# io-board-a-3.net
KiCad netlist of a schematic drawn in EAGLE
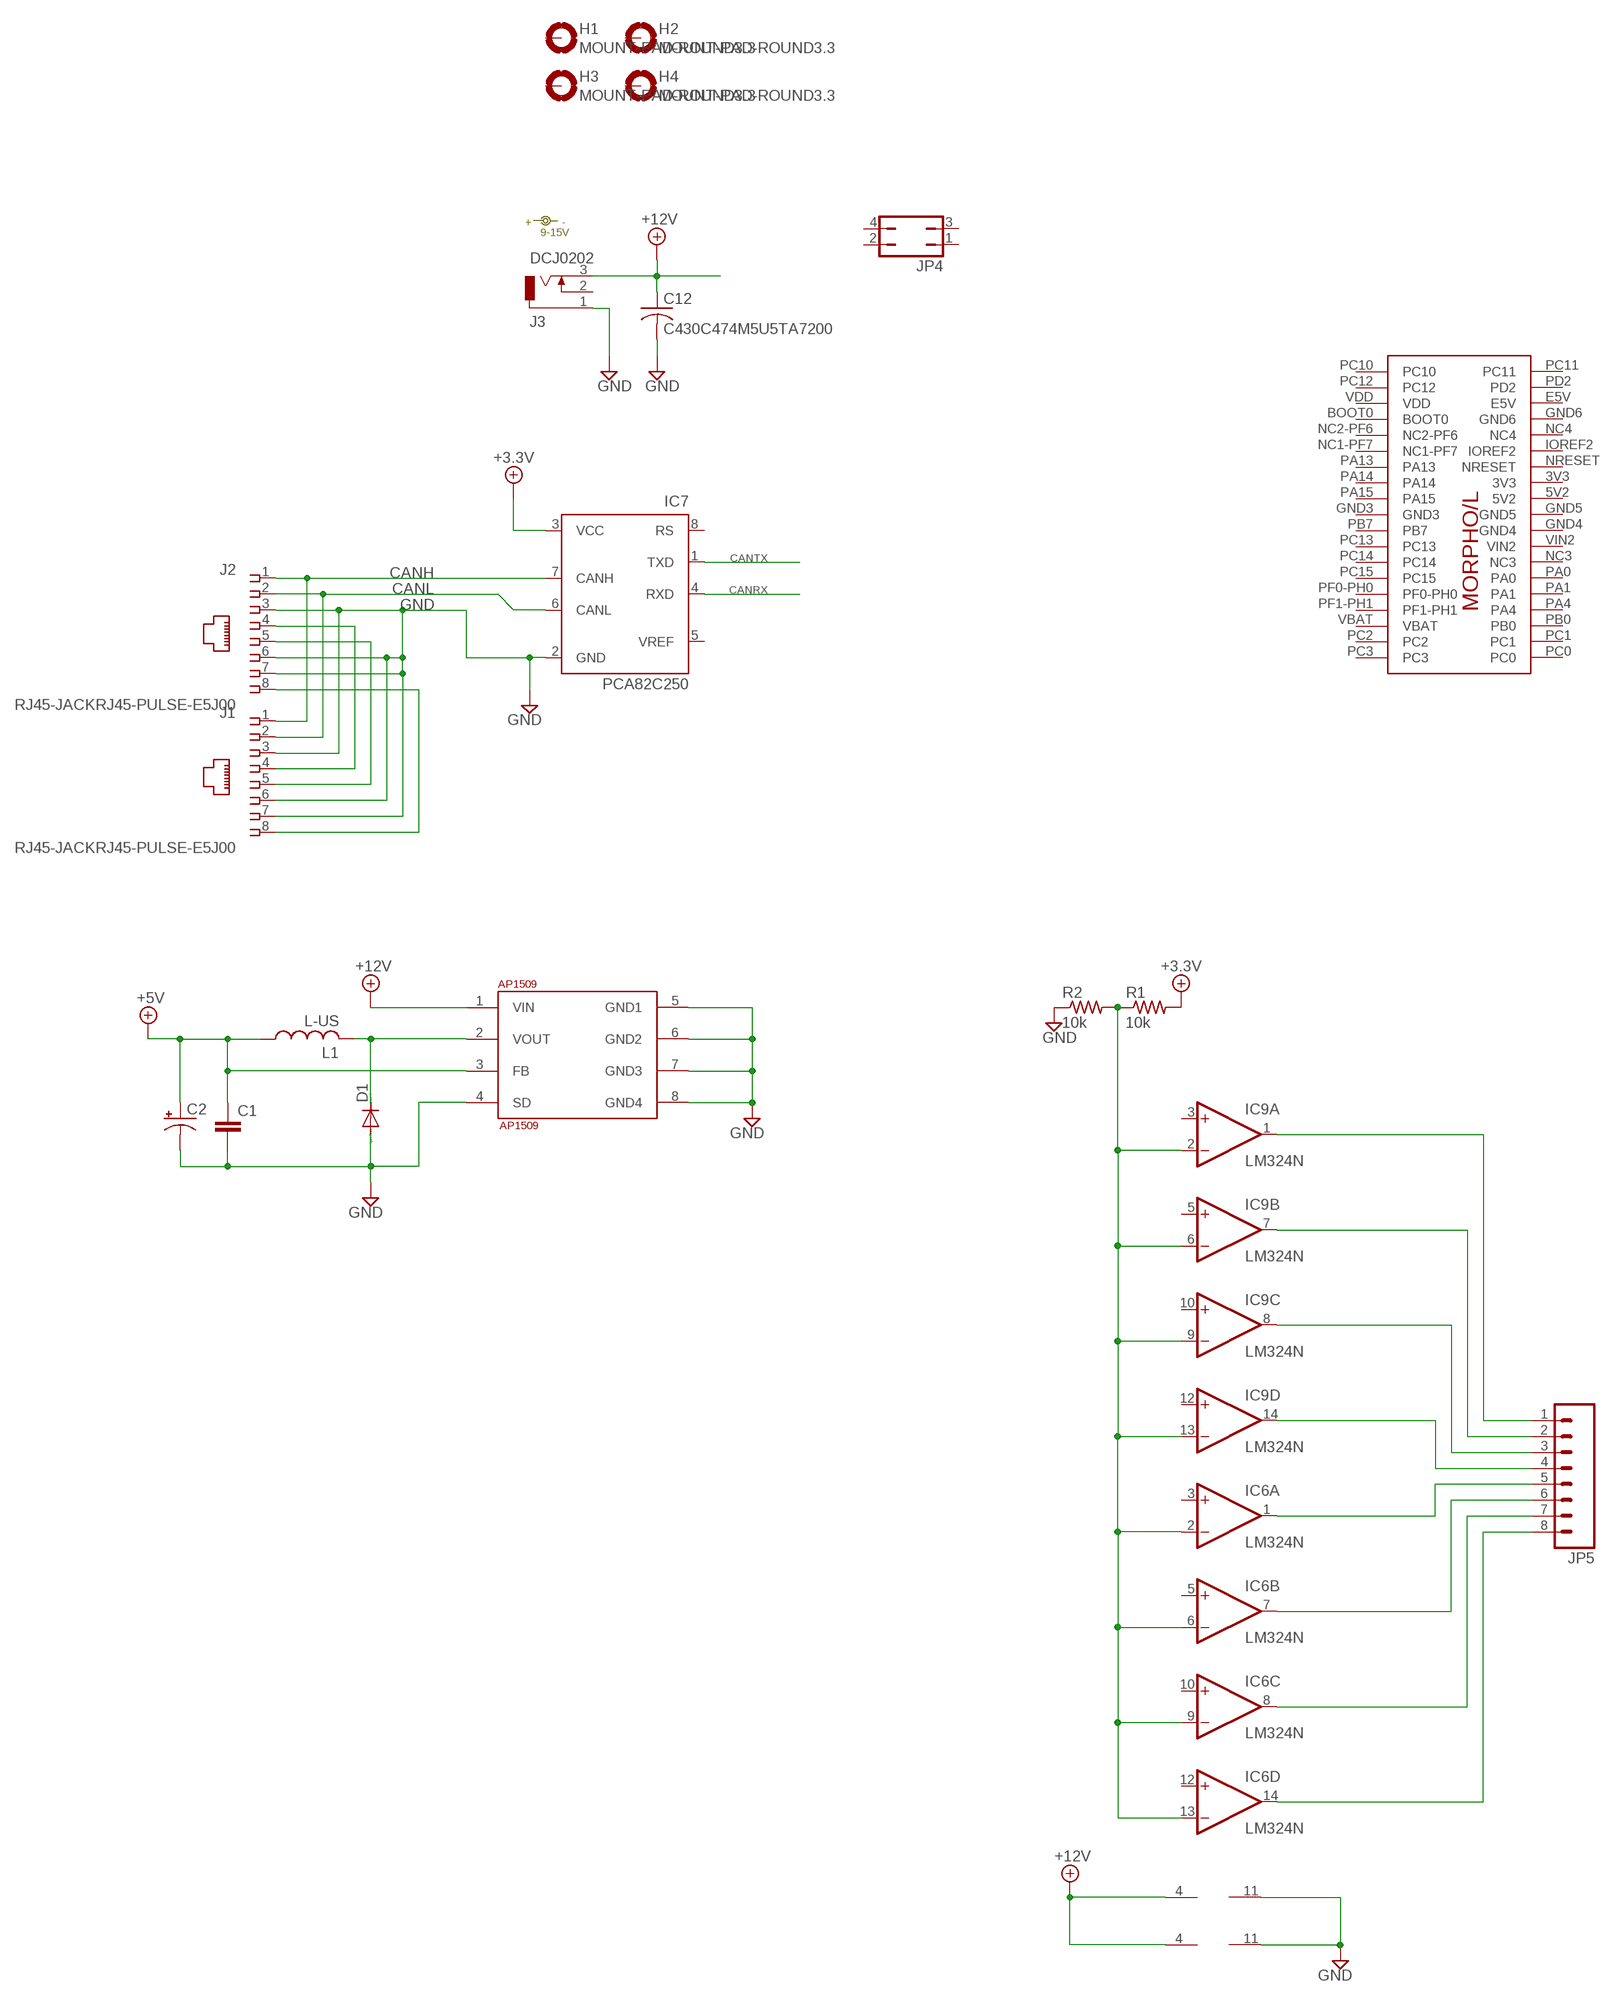
[diagram p0: schematic, sheet 1, part 1 of 2]
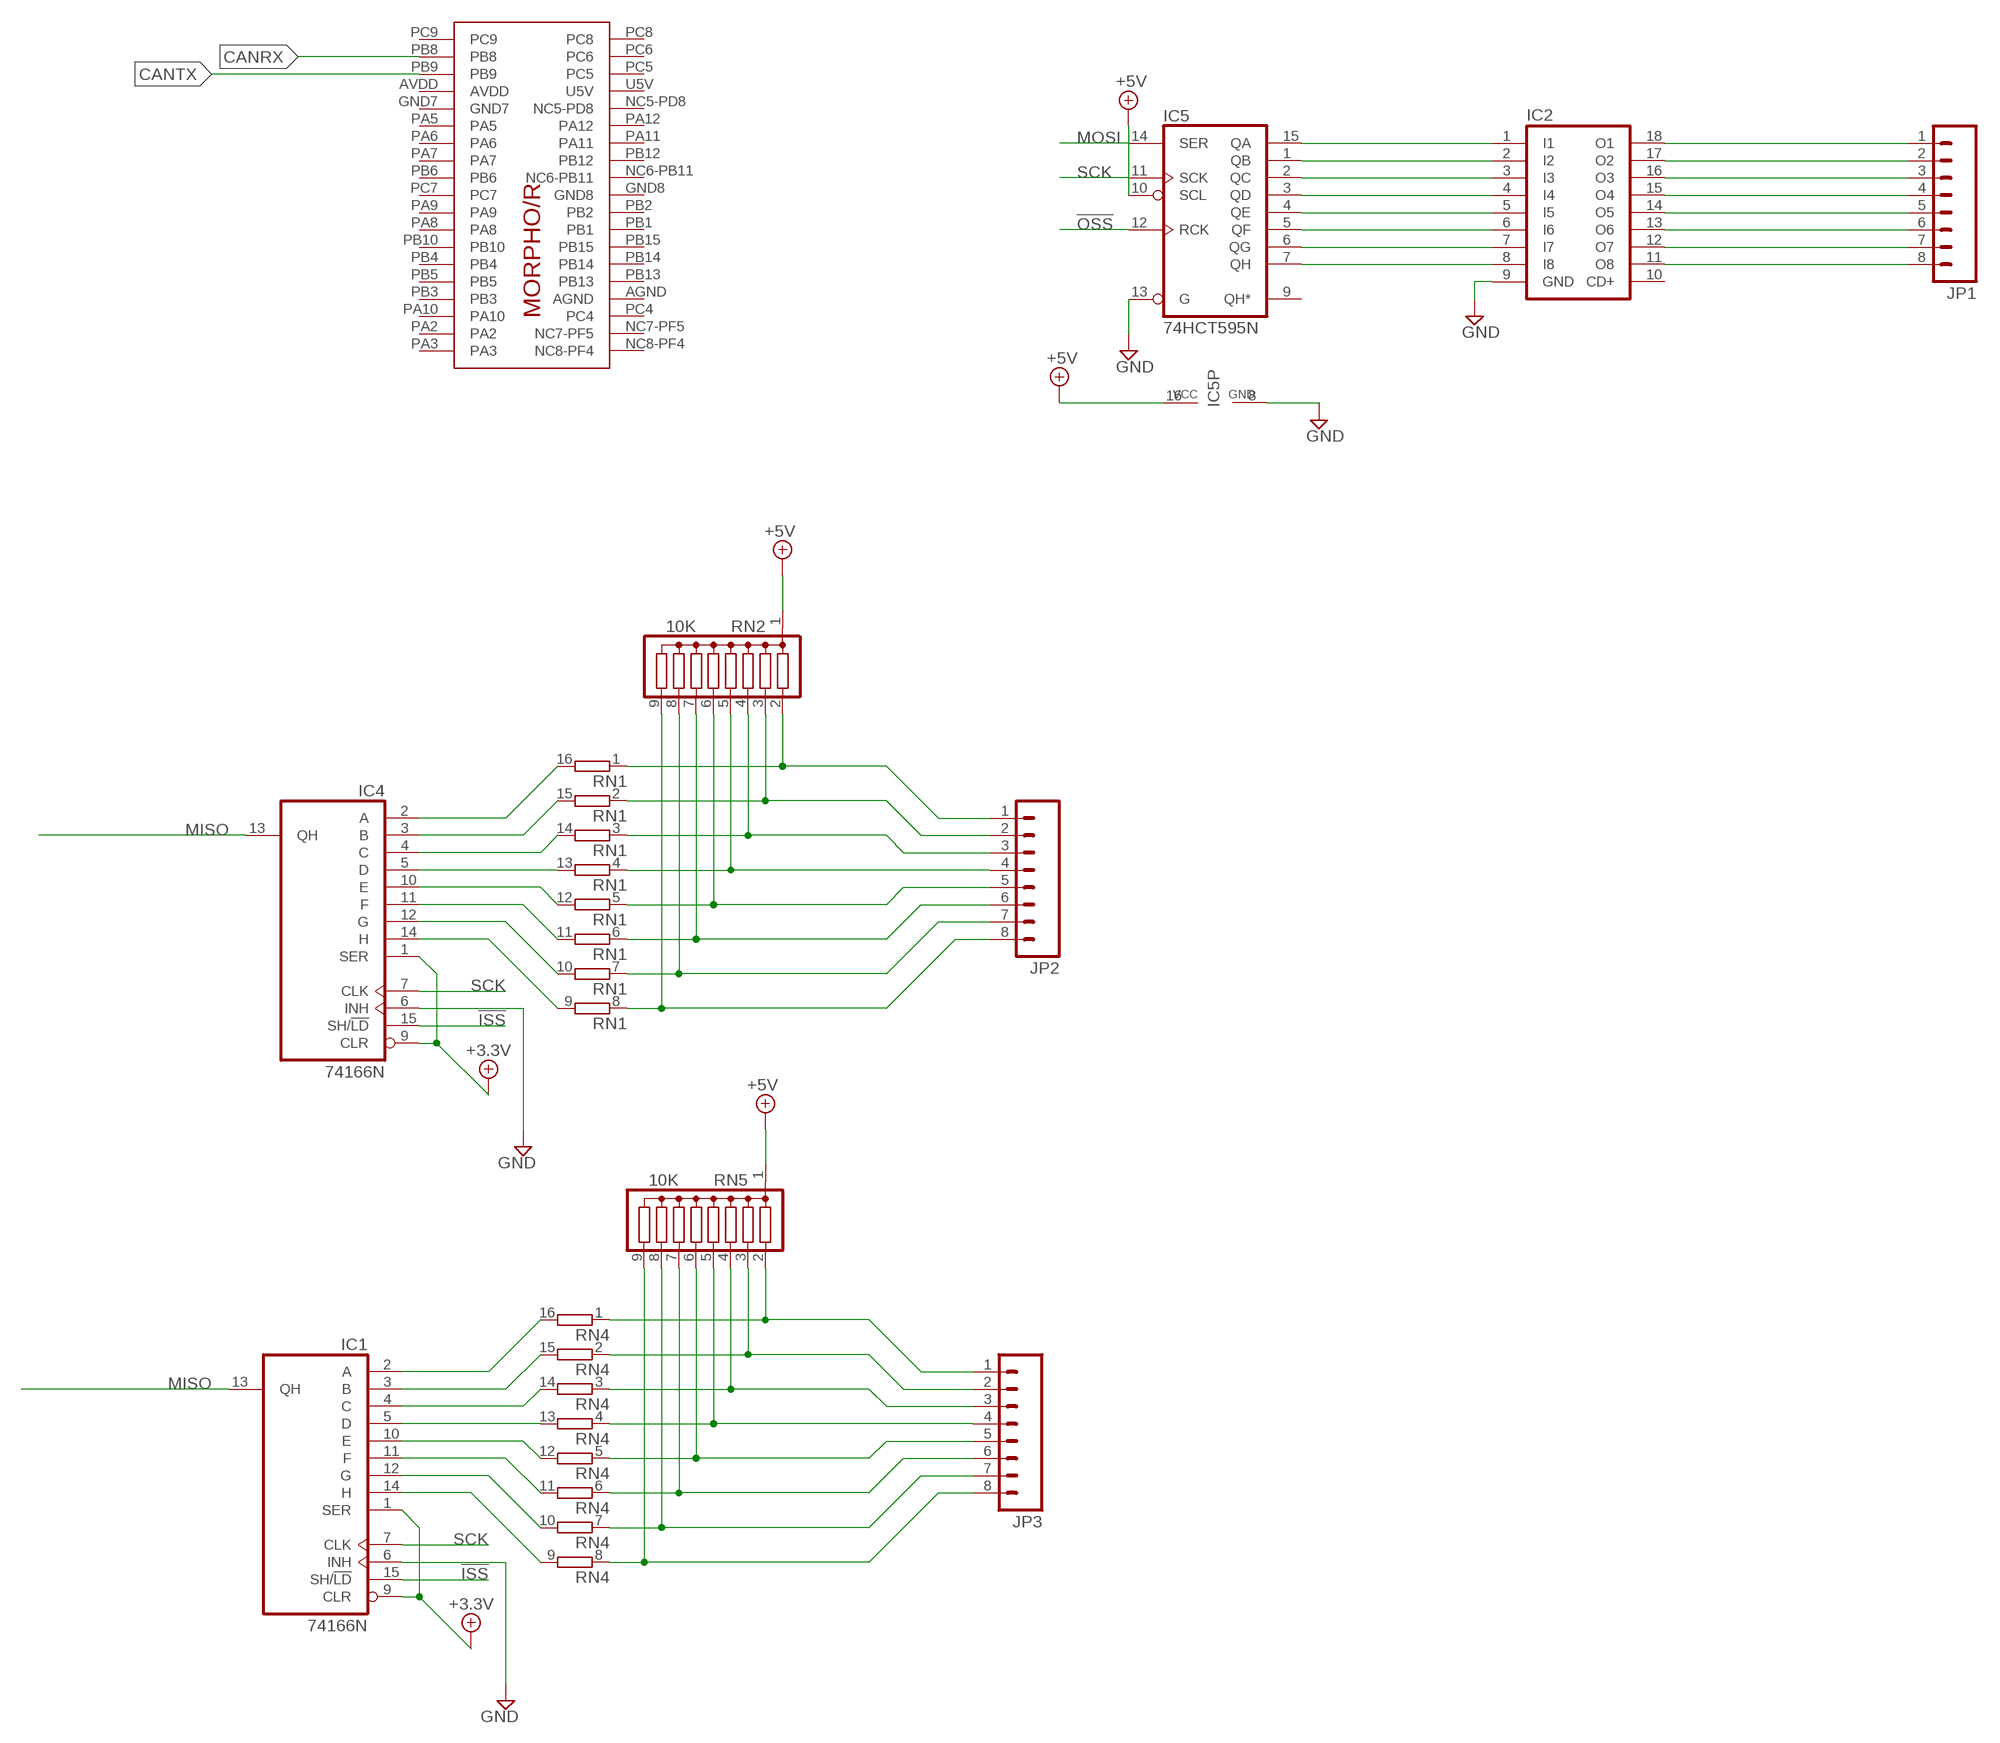
[diagram p1: schematic, sheet 1, part 2 of 2]

(export (version "E")
  (design (tool "Eeschema 10.0.6"))
  (components
    (comp (ref "+12V")
      (value "9-15V")
      (footprint "eagle-import:POWER_USAGE")
      (libsource (lib "eagle-import") (part "DOC-POWER_LABEL"))
    )
    (comp (ref "AP1509")
      (value "AP1509")
      (footprint "eagle-import:SO-08")
      (libsource (lib "eagle-import") (part "AP1509"))
    )
    (comp (ref "C1")
      (value "C-EUC1206")
      (footprint "eagle-import:C1206")
      (libsource (lib "eagle-import") (part "C-EUC1206"))
    )
    (comp (ref "C2")
      (value "CPOL-USE2.5-5")
      (footprint "eagle-import:E2,5-5")
      (libsource (lib "eagle-import") (part "CPOL-USE2.5-5"))
    )
    (comp (ref "C12")
      (value "C430C474M5U5TA7200")
      (footprint "eagle-import:C075-032X103")
      (libsource (lib "eagle-import") (part "C-US075-032X103"))
    )
    (comp (ref "D1")
      (value "DIODE-DO41-7.6")
      (footprint "eagle-import:DO41-7.6")
      (libsource (lib "eagle-import") (part "DIODE-DO41-7.6"))
    )
    (comp (ref "H1")
      (value "MOUNT-PAD-ROUND3.3")
      (footprint "eagle-import:3,3-PAD")
      (libsource (lib "eagle-import") (part "MOUNT-PAD-ROUND3.3"))
    )
    (comp (ref "H2")
      (value "MOUNT-PAD-ROUND3.3")
      (footprint "eagle-import:3,3-PAD")
      (libsource (lib "eagle-import") (part "MOUNT-PAD-ROUND3.3"))
    )
    (comp (ref "H3")
      (value "MOUNT-PAD-ROUND3.3")
      (footprint "eagle-import:3,3-PAD")
      (libsource (lib "eagle-import") (part "MOUNT-PAD-ROUND3.3"))
    )
    (comp (ref "H4")
      (value "MOUNT-PAD-ROUND3.3")
      (footprint "eagle-import:3,3-PAD")
      (libsource (lib "eagle-import") (part "MOUNT-PAD-ROUND3.3"))
    )
    (comp (ref "IC1")
      (value "74166N")
      (footprint "eagle-import:DIL16")
      (libsource (lib "eagle-import") (part "74166N"))
    )
    (comp (ref "IC2")
      (value "ULN2803A")
      (footprint "eagle-import:DIL18")
      (libsource (lib "eagle-import") (part "ULN2803A"))
    )
    (comp (ref "IC4")
      (value "74166N")
      (footprint "eagle-import:DIL16")
      (libsource (lib "eagle-import") (part "74166N"))
    )
    (comp (ref "IC5")
      (value "74HCT595N")
      (footprint "eagle-import:DIL16")
      (libsource (lib "eagle-import") (part "74595NHCT"))
    )
    (comp (ref "IC6")
      (value "LM324N")
      (footprint "eagle-import:DIL14")
      (libsource (lib "eagle-import") (part "LM324N"))
    )
    (comp (ref "IC7")
      (value "PCA82C250")
      (footprint "eagle-import:DIL08")
      (libsource (lib "eagle-import") (part "PCA82C250"))
    )
    (comp (ref "IC9")
      (value "LM324N")
      (footprint "eagle-import:DIL14")
      (libsource (lib "eagle-import") (part "LM324N"))
    )
    (comp (ref "J1")
      (value "RJ45-JACKRJ45-PULSE-E5J00")
      (footprint "eagle-import:RJ45-PULSE-E5J88")
      (libsource (lib "eagle-import") (part "RJ45-JACKRJ45-PULSE-E5J00"))
    )
    (comp (ref "J2")
      (value "RJ45-JACKRJ45-PULSE-E5J00")
      (footprint "eagle-import:RJ45-PULSE-E5J88")
      (libsource (lib "eagle-import") (part "RJ45-JACKRJ45-PULSE-E5J00"))
    )
    (comp (ref "J3")
      (value "DCJ0202")
      (footprint "eagle-import:DCJ0202")
      (libsource (lib "eagle-import") (part "DCJ0202"))
    )
    (comp (ref "JP1")
      (value "M08LOCK")
      (footprint "eagle-import:1X08_LOCK")
      (libsource (lib "eagle-import") (part "M08LOCK"))
    )
    (comp (ref "JP2")
      (value "M08LOCK")
      (footprint "eagle-import:1X08_LOCK")
      (libsource (lib "eagle-import") (part "M08LOCK"))
    )
    (comp (ref "JP3")
      (value "M08LOCK")
      (footprint "eagle-import:1X08_LOCK")
      (libsource (lib "eagle-import") (part "M08LOCK"))
    )
    (comp (ref "JP4")
      (value "JP2Q")
      (footprint "eagle-import:JP2Q")
      (libsource (lib "eagle-import") (part "JP2Q"))
    )
    (comp (ref "JP5")
      (value "M08LOCK")
      (footprint "eagle-import:1X08_LOCK")
      (libsource (lib "eagle-import") (part "M08LOCK"))
    )
    (comp (ref "L1")
      (value "L-US")
      (footprint "eagle-import:L5-8,5")
      (libsource (lib "eagle-import") (part "L-US"))
    )
    (comp (ref "R1")
      (value "10k")
      (footprint "eagle-import:R1206")
      (libsource (lib "eagle-import") (part "R-US_R1206"))
    )
    (comp (ref "R2")
      (value "10k")
      (footprint "eagle-import:R1206")
      (libsource (lib "eagle-import") (part "R-US_R1206"))
    )
    (comp (ref "RN1")
      (value "8R-P")
      (footprint "eagle-import:DIL16")
      (libsource (lib "eagle-import") (part "8R-P"))
    )
    (comp (ref "RN2")
      (value "10K")
      (footprint "eagle-import:SIL9")
      (libsource (lib "eagle-import") (part "G08R"))
    )
    (comp (ref "RN4")
      (value "8R-P")
      (footprint "eagle-import:DIL16")
      (libsource (lib "eagle-import") (part "8R-P"))
    )
    (comp (ref "RN5")
      (value "10K")
      (footprint "eagle-import:SIL9")
      (libsource (lib "eagle-import") (part "G08R"))
    )
    (comp (ref "U$1")
      (value "NUCLEO_64_GENERIC")
      (footprint "eagle-import:NUCLEO_BRD_BASE64")
      (libsource (lib "eagle-import") (part "NUCLEO_64_GENERIC"))
    )
  )
  (nets
    (net (code "1") (name "+3.3V") (class "Default")
      (node (ref "IC1") (pin "1") (pinfunction "SER_1") (pintype "input"))
      (node (ref "IC1") (pin "9") (pinfunction "CLR_9") (pintype "input"))
      (node (ref "IC4") (pin "1") (pinfunction "SER_1") (pintype "input"))
      (node (ref "IC4") (pin "9") (pinfunction "CLR_9") (pintype "input"))
      (node (ref "IC7") (pin "3") (pinfunction "VCC_3") (pintype "power_in"))
      (node (ref "R1") (pin "2") (pinfunction "2_2") (pintype "passive"))
    )
    (net (code "2") (name "+5V") (class "Default")
      (node (ref "AP1509") (pin "3") (pinfunction "FB_3") (pintype "bidirectional"))
      (node (ref "C1") (pin "1") (pinfunction "1_1") (pintype "passive"))
      (node (ref "C2") (pin "+") (pinfunction "+_+") (pintype "passive"))
      (node (ref "IC5") (pin "10") (pinfunction "SCL_10") (pintype "input"))
      (node (ref "IC5") (pin "16") (pinfunction "VCC_16") (pintype "power_in"))
      (node (ref "L1") (pin "1") (pinfunction "1_1") (pintype "passive"))
      (node (ref "RN2") (pin "1") (pinfunction "1_1") (pintype "passive"))
      (node (ref "RN5") (pin "1") (pinfunction "1_1") (pintype "passive"))
    )
    (net (code "3") (name "+12V") (class "Default")
      (node (ref "AP1509") (pin "1") (pinfunction "VIN_1") (pintype "bidirectional"))
      (node (ref "C12") (pin "1") (pinfunction "1_1") (pintype "passive"))
      (node (ref "IC6") (pin "4") (pinfunction "V+_4") (pintype "power_in"))
      (node (ref "IC9") (pin "4") (pinfunction "V+_4") (pintype "power_in"))
      (node (ref "J3") (pin "3") (pinfunction "3_3") (pintype "passive"))
    )
    (net (code "4") (name "/3V3") (class "Default")
      (node (ref "U$1") (pin "3V3") (pinfunction "3V3_3V3") (pintype "power_in"))
    )
    (net (code "5") (name "/5V2") (class "Default")
      (node (ref "U$1") (pin "5V2") (pinfunction "5V2_5V2") (pintype "power_in"))
    )
    (net (code "6") (name "/AGND") (class "Default")
      (node (ref "U$1") (pin "AGND") (pinfunction "AGND_AGND") (pintype "power_in"))
    )
    (net (code "7") (name "/AVDD") (class "Default")
      (node (ref "U$1") (pin "AVDD") (pinfunction "AVDD_AVDD") (pintype "power_in"))
    )
    (net (code "8") (name "/CANH") (class "Default")
      (node (ref "IC7") (pin "7") (pinfunction "CANH_7") (pintype "bidirectional"))
      (node (ref "J1") (pin "1") (pinfunction "1_1") (pintype "passive"))
      (node (ref "J2") (pin "1") (pinfunction "1_1") (pintype "passive"))
    )
    (net (code "9") (name "/CANL") (class "Default")
      (node (ref "IC7") (pin "6") (pinfunction "CANL_6") (pintype "bidirectional"))
      (node (ref "J1") (pin "2") (pinfunction "2_2") (pintype "passive"))
      (node (ref "J2") (pin "2") (pinfunction "2_2") (pintype "passive"))
    )
    (net (code "10") (name "/E5V") (class "Default")
      (node (ref "U$1") (pin "E5V") (pinfunction "E5V_E5V") (pintype "power_in"))
    )
    (net (code "11") (name "/GND3") (class "Default")
      (node (ref "U$1") (pin "GND3") (pinfunction "GND3_GND3") (pintype "power_in"))
    )
    (net (code "12") (name "/GND4") (class "Default")
      (node (ref "U$1") (pin "GND4") (pinfunction "GND4_GND4") (pintype "power_in"))
    )
    (net (code "13") (name "/GND5") (class "Default")
      (node (ref "U$1") (pin "GND5") (pinfunction "GND5_GND5") (pintype "power_in"))
    )
    (net (code "14") (name "/GND6") (class "Default")
      (node (ref "U$1") (pin "GND6") (pinfunction "GND6_GND6") (pintype "power_in"))
    )
    (net (code "15") (name "/GND7") (class "Default")
      (node (ref "U$1") (pin "GND7") (pinfunction "GND7_GND7") (pintype "power_in"))
    )
    (net (code "16") (name "/GND8") (class "Default")
      (node (ref "U$1") (pin "GND8") (pinfunction "GND8_GND8") (pintype "power_in"))
    )
    (net (code "17") (name "/MISO") (class "Default")
      (node (ref "IC1") (pin "13") (pinfunction "QH_13") (pintype "output"))
      (node (ref "IC4") (pin "13") (pinfunction "QH_13") (pintype "output"))
    )
    (net (code "18") (name "/MOSI") (class "Default")
      (node (ref "IC5") (pin "14") (pinfunction "SER_14") (pintype "input"))
    )
    (net (code "19") (name "/SCK") (class "Default")
      (node (ref "IC1") (pin "7") (pinfunction "CLK_7") (pintype "input"))
      (node (ref "IC4") (pin "7") (pinfunction "CLK_7") (pintype "input"))
      (node (ref "IC5") (pin "11") (pinfunction "SCK_11") (pintype "input"))
    )
    (net (code "20") (name "/U5V") (class "Default")
      (node (ref "U$1") (pin "U5V") (pinfunction "U5V_U5V") (pintype "power_in"))
    )
    (net (code "21") (name "/VBAT") (class "Default")
      (node (ref "U$1") (pin "VBAT") (pinfunction "VBAT_VBAT") (pintype "power_in"))
    )
    (net (code "22") (name "/VDD") (class "Default")
      (node (ref "U$1") (pin "VDD") (pinfunction "VDD_VDD") (pintype "power_in"))
    )
    (net (code "23") (name "/VIN2") (class "Default")
      (node (ref "U$1") (pin "VIN2") (pinfunction "VIN2_VIN2") (pintype "power_in"))
    )
    (net (code "24") (name "/~{ISS}") (class "Default")
      (node (ref "IC1") (pin "15") (pinfunction "SH/~{LD}_15") (pintype "input"))
      (node (ref "IC4") (pin "15") (pinfunction "SH/~{LD}_15") (pintype "input"))
    )
    (net (code "25") (name "/~{OSS}") (class "Default")
      (node (ref "IC5") (pin "12") (pinfunction "RCK_12") (pintype "input"))
    )
    (net (code "26") (name "CANRX") (class "Default")
      (node (ref "IC7") (pin "4") (pinfunction "RXD_4") (pintype "output"))
      (node (ref "U$1") (pin "PB8") (pinfunction "PB8_PB8") (pintype "bidirectional"))
    )
    (net (code "27") (name "CANTX") (class "Default")
      (node (ref "IC7") (pin "1") (pinfunction "TXD_1") (pintype "input"))
      (node (ref "U$1") (pin "PB9") (pinfunction "PB9_PB9") (pintype "bidirectional"))
    )
    (net (code "28") (name "GND") (class "Default")
      (node (ref "AP1509") (pin "4") (pinfunction "SD_4") (pintype "bidirectional"))
      (node (ref "AP1509") (pin "5") (pinfunction "GND1_5") (pintype "power_in"))
      (node (ref "AP1509") (pin "6") (pinfunction "GND2_6") (pintype "power_in"))
      (node (ref "AP1509") (pin "7") (pinfunction "GND3_7") (pintype "power_in"))
      (node (ref "AP1509") (pin "8") (pinfunction "GND4_8") (pintype "power_in"))
      (node (ref "C1") (pin "2") (pinfunction "2_2") (pintype "passive"))
      (node (ref "C12") (pin "2") (pinfunction "2_2") (pintype "passive"))
      (node (ref "C2") (pin "-") (pinfunction "-_-") (pintype "passive"))
      (node (ref "D1") (pin "A") (pinfunction "A_A") (pintype "passive"))
      (node (ref "IC1") (pin "6") (pinfunction "INH_6") (pintype "input"))
      (node (ref "IC2") (pin "9") (pinfunction "GND_9") (pintype "power_in"))
      (node (ref "IC4") (pin "6") (pinfunction "INH_6") (pintype "input"))
      (node (ref "IC5") (pin "13") (pinfunction "G_13") (pintype "input"))
      (node (ref "IC5") (pin "8") (pinfunction "GND_8") (pintype "power_in"))
      (node (ref "IC6") (pin "11") (pinfunction "V-_11") (pintype "power_in"))
      (node (ref "IC7") (pin "2") (pinfunction "GND_2") (pintype "power_in"))
      (node (ref "IC9") (pin "11") (pinfunction "V-_11") (pintype "power_in"))
      (node (ref "J1") (pin "3") (pinfunction "3_3") (pintype "passive"))
      (node (ref "J1") (pin "6") (pinfunction "6_6") (pintype "passive"))
      (node (ref "J1") (pin "7") (pinfunction "7_7") (pintype "passive"))
      (node (ref "J2") (pin "3") (pinfunction "3_3") (pintype "passive"))
      (node (ref "J2") (pin "6") (pinfunction "6_6") (pintype "passive"))
      (node (ref "J2") (pin "7") (pinfunction "7_7") (pintype "passive"))
      (node (ref "J3") (pin "1") (pinfunction "1_1") (pintype "passive"))
      (node (ref "R2") (pin "1") (pinfunction "1_1") (pintype "passive"))
    )
    (net (code "29") (name "Net-(AP1509-VOUT)") (class "Default")
      (node (ref "AP1509") (pin "2") (pinfunction "VOUT_2") (pintype "bidirectional"))
      (node (ref "D1") (pin "C") (pinfunction "C_C") (pintype "passive"))
      (node (ref "L1") (pin "2") (pinfunction "2_2") (pintype "passive"))
    )
    (net (code "30") (name "Net-(IC1A-A)") (class "Default")
      (node (ref "IC1") (pin "2") (pinfunction "A_2") (pintype "input"))
      (node (ref "RN4") (pin "16") (pinfunction "2_16") (pintype "passive"))
    )
    (net (code "31") (name "Net-(IC1A-B)") (class "Default")
      (node (ref "IC1") (pin "3") (pinfunction "B_3") (pintype "input"))
      (node (ref "RN4") (pin "15") (pinfunction "2_15") (pintype "passive"))
    )
    (net (code "32") (name "Net-(IC1A-C)") (class "Default")
      (node (ref "IC1") (pin "4") (pinfunction "C_4") (pintype "input"))
      (node (ref "RN4") (pin "14") (pinfunction "2_14") (pintype "passive"))
    )
    (net (code "33") (name "Net-(IC1A-D)") (class "Default")
      (node (ref "IC1") (pin "5") (pinfunction "D_5") (pintype "input"))
      (node (ref "RN4") (pin "13") (pinfunction "2_13") (pintype "passive"))
    )
    (net (code "34") (name "Net-(IC1A-E)") (class "Default")
      (node (ref "IC1") (pin "10") (pinfunction "E_10") (pintype "input"))
      (node (ref "RN4") (pin "12") (pinfunction "2_12") (pintype "passive"))
    )
    (net (code "35") (name "Net-(IC1A-F)") (class "Default")
      (node (ref "IC1") (pin "11") (pinfunction "F_11") (pintype "input"))
      (node (ref "RN4") (pin "11") (pinfunction "2_11") (pintype "passive"))
    )
    (net (code "36") (name "Net-(IC1A-G)") (class "Default")
      (node (ref "IC1") (pin "12") (pinfunction "G_12") (pintype "input"))
      (node (ref "RN4") (pin "10") (pinfunction "2_10") (pintype "passive"))
    )
    (net (code "37") (name "Net-(IC1A-H)") (class "Default")
      (node (ref "IC1") (pin "14") (pinfunction "H_14") (pintype "input"))
      (node (ref "RN4") (pin "9") (pinfunction "2_9") (pintype "passive"))
    )
    (net (code "38") (name "Net-(IC2-I1)") (class "Default")
      (node (ref "IC2") (pin "1") (pinfunction "I1_1") (pintype "input"))
      (node (ref "IC5") (pin "15") (pinfunction "QA_15") (pintype "tri_state"))
    )
    (net (code "39") (name "Net-(IC2-I2)") (class "Default")
      (node (ref "IC2") (pin "2") (pinfunction "I2_2") (pintype "input"))
      (node (ref "IC5") (pin "1") (pinfunction "QB_1") (pintype "tri_state"))
    )
    (net (code "40") (name "Net-(IC2-I3)") (class "Default")
      (node (ref "IC2") (pin "3") (pinfunction "I3_3") (pintype "input"))
      (node (ref "IC5") (pin "2") (pinfunction "QC_2") (pintype "tri_state"))
    )
    (net (code "41") (name "Net-(IC2-I4)") (class "Default")
      (node (ref "IC2") (pin "4") (pinfunction "I4_4") (pintype "input"))
      (node (ref "IC5") (pin "3") (pinfunction "QD_3") (pintype "tri_state"))
    )
    (net (code "42") (name "Net-(IC2-I5)") (class "Default")
      (node (ref "IC2") (pin "5") (pinfunction "I5_5") (pintype "input"))
      (node (ref "IC5") (pin "4") (pinfunction "QE_4") (pintype "tri_state"))
    )
    (net (code "43") (name "Net-(IC2-I6)") (class "Default")
      (node (ref "IC2") (pin "6") (pinfunction "I6_6") (pintype "input"))
      (node (ref "IC5") (pin "5") (pinfunction "QF_5") (pintype "tri_state"))
    )
    (net (code "44") (name "Net-(IC2-I7)") (class "Default")
      (node (ref "IC2") (pin "7") (pinfunction "I7_7") (pintype "input"))
      (node (ref "IC5") (pin "6") (pinfunction "QG_6") (pintype "tri_state"))
    )
    (net (code "45") (name "Net-(IC2-I8)") (class "Default")
      (node (ref "IC2") (pin "8") (pinfunction "I8_8") (pintype "input"))
      (node (ref "IC5") (pin "7") (pinfunction "QH_7") (pintype "tri_state"))
    )
    (net (code "46") (name "Net-(IC2-O1)") (class "Default")
      (node (ref "IC2") (pin "18") (pinfunction "O1_18") (pintype "open_collector"))
      (node (ref "JP1") (pin "1") (pinfunction "1_1") (pintype "passive"))
    )
    (net (code "47") (name "Net-(IC2-O2)") (class "Default")
      (node (ref "IC2") (pin "17") (pinfunction "O2_17") (pintype "open_collector"))
      (node (ref "JP1") (pin "2") (pinfunction "2_2") (pintype "passive"))
    )
    (net (code "48") (name "Net-(IC2-O3)") (class "Default")
      (node (ref "IC2") (pin "16") (pinfunction "O3_16") (pintype "open_collector"))
      (node (ref "JP1") (pin "3") (pinfunction "3_3") (pintype "passive"))
    )
    (net (code "49") (name "Net-(IC2-O4)") (class "Default")
      (node (ref "IC2") (pin "15") (pinfunction "O4_15") (pintype "open_collector"))
      (node (ref "JP1") (pin "4") (pinfunction "4_4") (pintype "passive"))
    )
    (net (code "50") (name "Net-(IC2-O5)") (class "Default")
      (node (ref "IC2") (pin "14") (pinfunction "O5_14") (pintype "open_collector"))
      (node (ref "JP1") (pin "5") (pinfunction "5_5") (pintype "passive"))
    )
    (net (code "51") (name "Net-(IC2-O6)") (class "Default")
      (node (ref "IC2") (pin "13") (pinfunction "O6_13") (pintype "open_collector"))
      (node (ref "JP1") (pin "6") (pinfunction "6_6") (pintype "passive"))
    )
    (net (code "52") (name "Net-(IC2-O7)") (class "Default")
      (node (ref "IC2") (pin "12") (pinfunction "O7_12") (pintype "open_collector"))
      (node (ref "JP1") (pin "7") (pinfunction "7_7") (pintype "passive"))
    )
    (net (code "53") (name "Net-(IC2-O8)") (class "Default")
      (node (ref "IC2") (pin "11") (pinfunction "O8_11") (pintype "open_collector"))
      (node (ref "JP1") (pin "8") (pinfunction "8_8") (pintype "passive"))
    )
    (net (code "54") (name "Net-(IC4A-A)") (class "Default")
      (node (ref "IC4") (pin "2") (pinfunction "A_2") (pintype "input"))
      (node (ref "RN1") (pin "16") (pinfunction "2_16") (pintype "passive"))
    )
    (net (code "55") (name "Net-(IC4A-B)") (class "Default")
      (node (ref "IC4") (pin "3") (pinfunction "B_3") (pintype "input"))
      (node (ref "RN1") (pin "15") (pinfunction "2_15") (pintype "passive"))
    )
    (net (code "56") (name "Net-(IC4A-C)") (class "Default")
      (node (ref "IC4") (pin "4") (pinfunction "C_4") (pintype "input"))
      (node (ref "RN1") (pin "14") (pinfunction "2_14") (pintype "passive"))
    )
    (net (code "57") (name "Net-(IC4A-D)") (class "Default")
      (node (ref "IC4") (pin "5") (pinfunction "D_5") (pintype "input"))
      (node (ref "RN1") (pin "13") (pinfunction "2_13") (pintype "passive"))
    )
    (net (code "58") (name "Net-(IC4A-E)") (class "Default")
      (node (ref "IC4") (pin "10") (pinfunction "E_10") (pintype "input"))
      (node (ref "RN1") (pin "12") (pinfunction "2_12") (pintype "passive"))
    )
    (net (code "59") (name "Net-(IC4A-F)") (class "Default")
      (node (ref "IC4") (pin "11") (pinfunction "F_11") (pintype "input"))
      (node (ref "RN1") (pin "11") (pinfunction "2_11") (pintype "passive"))
    )
    (net (code "60") (name "Net-(IC4A-G)") (class "Default")
      (node (ref "IC4") (pin "12") (pinfunction "G_12") (pintype "input"))
      (node (ref "RN1") (pin "10") (pinfunction "2_10") (pintype "passive"))
    )
    (net (code "61") (name "Net-(IC4A-H)") (class "Default")
      (node (ref "IC4") (pin "14") (pinfunction "H_14") (pintype "input"))
      (node (ref "RN1") (pin "9") (pinfunction "2_9") (pintype "passive"))
    )
    (net (code "62") (name "Net-(IC6A--IN)") (class "Default")
      (node (ref "IC6") (pin "13") (pinfunction "-IN_13") (pintype "input"))
      (node (ref "IC6") (pin "2") (pinfunction "-IN_2") (pintype "input"))
      (node (ref "IC6") (pin "6") (pinfunction "-IN_6") (pintype "input"))
      (node (ref "IC6") (pin "9") (pinfunction "-IN_9") (pintype "input"))
      (node (ref "IC9") (pin "13") (pinfunction "-IN_13") (pintype "input"))
      (node (ref "IC9") (pin "2") (pinfunction "-IN_2") (pintype "input"))
      (node (ref "IC9") (pin "6") (pinfunction "-IN_6") (pintype "input"))
      (node (ref "IC9") (pin "9") (pinfunction "-IN_9") (pintype "input"))
      (node (ref "R1") (pin "1") (pinfunction "1_1") (pintype "passive"))
      (node (ref "R2") (pin "2") (pinfunction "2_2") (pintype "passive"))
    )
    (net (code "63") (name "Net-(IC6A-OUT)") (class "Default")
      (node (ref "IC6") (pin "1") (pinfunction "OUT_1") (pintype "output"))
      (node (ref "JP5") (pin "5") (pinfunction "5_5") (pintype "passive"))
    )
    (net (code "64") (name "Net-(IC6B-OUT)") (class "Default")
      (node (ref "IC6") (pin "7") (pinfunction "OUT_7") (pintype "output"))
      (node (ref "JP5") (pin "6") (pinfunction "6_6") (pintype "passive"))
    )
    (net (code "65") (name "Net-(IC6C-OUT)") (class "Default")
      (node (ref "IC6") (pin "8") (pinfunction "OUT_8") (pintype "output"))
      (node (ref "JP5") (pin "7") (pinfunction "7_7") (pintype "passive"))
    )
    (net (code "66") (name "Net-(IC6D-OUT)") (class "Default")
      (node (ref "IC6") (pin "14") (pinfunction "OUT_14") (pintype "output"))
      (node (ref "JP5") (pin "8") (pinfunction "8_8") (pintype "passive"))
    )
    (net (code "67") (name "Net-(IC9A-OUT)") (class "Default")
      (node (ref "IC9") (pin "1") (pinfunction "OUT_1") (pintype "output"))
      (node (ref "JP5") (pin "1") (pinfunction "1_1") (pintype "passive"))
    )
    (net (code "68") (name "Net-(IC9B-OUT)") (class "Default")
      (node (ref "IC9") (pin "7") (pinfunction "OUT_7") (pintype "output"))
      (node (ref "JP5") (pin "2") (pinfunction "2_2") (pintype "passive"))
    )
    (net (code "69") (name "Net-(IC9C-OUT)") (class "Default")
      (node (ref "IC9") (pin "8") (pinfunction "OUT_8") (pintype "output"))
      (node (ref "JP5") (pin "3") (pinfunction "3_3") (pintype "passive"))
    )
    (net (code "70") (name "Net-(IC9D-OUT)") (class "Default")
      (node (ref "IC9") (pin "14") (pinfunction "OUT_14") (pintype "output"))
      (node (ref "JP5") (pin "4") (pinfunction "4_4") (pintype "passive"))
    )
    (net (code "71") (name "Net-(J1-Pad4)") (class "Default")
      (node (ref "J1") (pin "4") (pinfunction "4_4") (pintype "passive"))
      (node (ref "J2") (pin "4") (pinfunction "4_4") (pintype "passive"))
    )
    (net (code "72") (name "Net-(J1-Pad5)") (class "Default")
      (node (ref "J1") (pin "5") (pinfunction "5_5") (pintype "passive"))
      (node (ref "J2") (pin "5") (pinfunction "5_5") (pintype "passive"))
    )
    (net (code "73") (name "Net-(J1-Pad8)") (class "Default")
      (node (ref "J1") (pin "8") (pinfunction "8_8") (pintype "passive"))
      (node (ref "J2") (pin "8") (pinfunction "8_8") (pintype "passive"))
    )
    (net (code "74") (name "Net-(JP2-Pad1)") (class "Default")
      (node (ref "JP2") (pin "1") (pinfunction "1_1") (pintype "passive"))
      (node (ref "RN1") (pin "1") (pinfunction "1_1") (pintype "passive"))
      (node (ref "RN2") (pin "2") (pinfunction "2_2") (pintype "passive"))
    )
    (net (code "75") (name "Net-(JP3-Pad1)") (class "Default")
      (node (ref "JP3") (pin "1") (pinfunction "1_1") (pintype "passive"))
      (node (ref "RN4") (pin "1") (pinfunction "1_1") (pintype "passive"))
      (node (ref "RN5") (pin "2") (pinfunction "2_2") (pintype "passive"))
    )
    (net (code "76") (name "Net-(RN1B-1)") (class "Default")
      (node (ref "JP2") (pin "2") (pinfunction "2_2") (pintype "passive"))
      (node (ref "RN1") (pin "2") (pinfunction "1_2") (pintype "passive"))
      (node (ref "RN2") (pin "3") (pinfunction "3_3") (pintype "passive"))
    )
    (net (code "77") (name "Net-(RN1C-1)") (class "Default")
      (node (ref "JP2") (pin "3") (pinfunction "3_3") (pintype "passive"))
      (node (ref "RN1") (pin "3") (pinfunction "1_3") (pintype "passive"))
      (node (ref "RN2") (pin "4") (pinfunction "4_4") (pintype "passive"))
    )
    (net (code "78") (name "Net-(RN1D-1)") (class "Default")
      (node (ref "JP2") (pin "4") (pinfunction "4_4") (pintype "passive"))
      (node (ref "RN1") (pin "4") (pinfunction "1_4") (pintype "passive"))
      (node (ref "RN2") (pin "5") (pinfunction "5_5") (pintype "passive"))
    )
    (net (code "79") (name "Net-(RN1E-1)") (class "Default")
      (node (ref "JP2") (pin "5") (pinfunction "5_5") (pintype "passive"))
      (node (ref "RN1") (pin "5") (pinfunction "1_5") (pintype "passive"))
      (node (ref "RN2") (pin "6") (pinfunction "6_6") (pintype "passive"))
    )
    (net (code "80") (name "Net-(RN1F-1)") (class "Default")
      (node (ref "JP2") (pin "6") (pinfunction "6_6") (pintype "passive"))
      (node (ref "RN1") (pin "6") (pinfunction "1_6") (pintype "passive"))
      (node (ref "RN2") (pin "7") (pinfunction "7_7") (pintype "passive"))
    )
    (net (code "81") (name "Net-(RN1G-1)") (class "Default")
      (node (ref "JP2") (pin "7") (pinfunction "7_7") (pintype "passive"))
      (node (ref "RN1") (pin "7") (pinfunction "1_7") (pintype "passive"))
      (node (ref "RN2") (pin "8") (pinfunction "8_8") (pintype "passive"))
    )
    (net (code "82") (name "Net-(RN1H-1)") (class "Default")
      (node (ref "JP2") (pin "8") (pinfunction "8_8") (pintype "passive"))
      (node (ref "RN1") (pin "8") (pinfunction "1_8") (pintype "passive"))
      (node (ref "RN2") (pin "9") (pinfunction "9_9") (pintype "passive"))
    )
    (net (code "83") (name "Net-(RN4B-1)") (class "Default")
      (node (ref "JP3") (pin "2") (pinfunction "2_2") (pintype "passive"))
      (node (ref "RN4") (pin "2") (pinfunction "1_2") (pintype "passive"))
      (node (ref "RN5") (pin "3") (pinfunction "3_3") (pintype "passive"))
    )
    (net (code "84") (name "Net-(RN4C-1)") (class "Default")
      (node (ref "JP3") (pin "3") (pinfunction "3_3") (pintype "passive"))
      (node (ref "RN4") (pin "3") (pinfunction "1_3") (pintype "passive"))
      (node (ref "RN5") (pin "4") (pinfunction "4_4") (pintype "passive"))
    )
    (net (code "85") (name "Net-(RN4D-1)") (class "Default")
      (node (ref "JP3") (pin "4") (pinfunction "4_4") (pintype "passive"))
      (node (ref "RN4") (pin "4") (pinfunction "1_4") (pintype "passive"))
      (node (ref "RN5") (pin "5") (pinfunction "5_5") (pintype "passive"))
    )
    (net (code "86") (name "Net-(RN4E-1)") (class "Default")
      (node (ref "JP3") (pin "5") (pinfunction "5_5") (pintype "passive"))
      (node (ref "RN4") (pin "5") (pinfunction "1_5") (pintype "passive"))
      (node (ref "RN5") (pin "6") (pinfunction "6_6") (pintype "passive"))
    )
    (net (code "87") (name "Net-(RN4F-1)") (class "Default")
      (node (ref "JP3") (pin "6") (pinfunction "6_6") (pintype "passive"))
      (node (ref "RN4") (pin "6") (pinfunction "1_6") (pintype "passive"))
      (node (ref "RN5") (pin "7") (pinfunction "7_7") (pintype "passive"))
    )
    (net (code "88") (name "Net-(RN4G-1)") (class "Default")
      (node (ref "JP3") (pin "7") (pinfunction "7_7") (pintype "passive"))
      (node (ref "RN4") (pin "7") (pinfunction "1_7") (pintype "passive"))
      (node (ref "RN5") (pin "8") (pinfunction "8_8") (pintype "passive"))
    )
    (net (code "89") (name "Net-(RN4H-1)") (class "Default")
      (node (ref "JP3") (pin "8") (pinfunction "8_8") (pintype "passive"))
      (node (ref "RN4") (pin "8") (pinfunction "1_8") (pintype "passive"))
      (node (ref "RN5") (pin "9") (pinfunction "9_9") (pintype "passive"))
    )
    (net (code "90") (name "unconnected-(H1-MOUNT-PadB3,3)") (class "Default")
      (node (ref "H1") (pin "B3,3") (pinfunction "MOUNT_B3,3") (pintype "passive"))
    )
    (net (code "91") (name "unconnected-(H2-MOUNT-PadB3,3)") (class "Default")
      (node (ref "H2") (pin "B3,3") (pinfunction "MOUNT_B3,3") (pintype "passive"))
    )
    (net (code "92") (name "unconnected-(H3-MOUNT-PadB3,3)") (class "Default")
      (node (ref "H3") (pin "B3,3") (pinfunction "MOUNT_B3,3") (pintype "passive"))
    )
    (net (code "93") (name "unconnected-(H4-MOUNT-PadB3,3)") (class "Default")
      (node (ref "H4") (pin "B3,3") (pinfunction "MOUNT_B3,3") (pintype "passive"))
    )
    (net (code "94") (name "unconnected-(IC2-CD+-Pad10)") (class "Default")
      (node (ref "IC2") (pin "10") (pinfunction "CD+_10") (pintype "passive"))
    )
    (net (code "95") (name "unconnected-(IC5A-QH*-Pad9)") (class "Default")
      (node (ref "IC5") (pin "9") (pinfunction "QH*_9") (pintype "tri_state"))
    )
    (net (code "96") (name "unconnected-(IC6A-+IN-Pad3)") (class "Default")
      (node (ref "IC6") (pin "3") (pinfunction "+IN_3") (pintype "input"))
    )
    (net (code "97") (name "unconnected-(IC6B-+IN-Pad5)") (class "Default")
      (node (ref "IC6") (pin "5") (pinfunction "+IN_5") (pintype "input"))
    )
    (net (code "98") (name "unconnected-(IC6C-+IN-Pad10)") (class "Default")
      (node (ref "IC6") (pin "10") (pinfunction "+IN_10") (pintype "input"))
    )
    (net (code "99") (name "unconnected-(IC6D-+IN-Pad12)") (class "Default")
      (node (ref "IC6") (pin "12") (pinfunction "+IN_12") (pintype "input"))
    )
    (net (code "100") (name "unconnected-(IC7-RS-Pad8)") (class "Default")
      (node (ref "IC7") (pin "8") (pinfunction "RS_8") (pintype "input"))
    )
    (net (code "101") (name "unconnected-(IC7-VREF-Pad5)") (class "Default")
      (node (ref "IC7") (pin "5") (pinfunction "VREF_5") (pintype "output"))
    )
    (net (code "102") (name "unconnected-(IC9A-+IN-Pad3)") (class "Default")
      (node (ref "IC9") (pin "3") (pinfunction "+IN_3") (pintype "input"))
    )
    (net (code "103") (name "unconnected-(IC9B-+IN-Pad5)") (class "Default")
      (node (ref "IC9") (pin "5") (pinfunction "+IN_5") (pintype "input"))
    )
    (net (code "104") (name "unconnected-(IC9C-+IN-Pad10)") (class "Default")
      (node (ref "IC9") (pin "10") (pinfunction "+IN_10") (pintype "input"))
    )
    (net (code "105") (name "unconnected-(IC9D-+IN-Pad12)") (class "Default")
      (node (ref "IC9") (pin "12") (pinfunction "+IN_12") (pintype "input"))
    )
    (net (code "106") (name "unconnected-(J3-Pad2)") (class "Default")
      (node (ref "J3") (pin "2") (pinfunction "2_2") (pintype "passive"))
    )
    (net (code "107") (name "unconnected-(JP4-Pad1)") (class "Default")
      (node (ref "JP4") (pin "1") (pinfunction "1_1") (pintype "passive"))
    )
    (net (code "108") (name "unconnected-(JP4-Pad2)") (class "Default")
      (node (ref "JP4") (pin "2") (pinfunction "2_2") (pintype "passive"))
    )
    (net (code "109") (name "unconnected-(JP4-Pad3)") (class "Default")
      (node (ref "JP4") (pin "3") (pinfunction "3_3") (pintype "passive"))
    )
    (net (code "110") (name "unconnected-(JP4-Pad4)") (class "Default")
      (node (ref "JP4") (pin "4") (pinfunction "4_4") (pintype "passive"))
    )
    (net (code "111") (name "unconnected-(U$1-PadBOOT0)") (class "Default")
      (node (ref "U$1") (pin "BOOT0") (pinfunction "BOOT0_BOOT0") (pintype "bidirectional"))
    )
    (net (code "112") (name "unconnected-(U$1-PadIOREF2)") (class "Default")
      (node (ref "U$1") (pin "IOREF2") (pinfunction "IOREF2_IOREF2") (pintype "input"))
    )
    (net (code "113") (name "unconnected-(U$1-PadNC1-PF7)") (class "Default")
      (node (ref "U$1") (pin "NC1-PF7") (pinfunction "NC1-PF7_NC1-PF7") (pintype "bidirectional"))
    )
    (net (code "114") (name "unconnected-(U$1-PadNC2-PF6)") (class "Default")
      (node (ref "U$1") (pin "NC2-PF6") (pinfunction "NC2-PF6_NC2-PF6") (pintype "bidirectional"))
    )
    (net (code "115") (name "unconnected-(U$1-PadNC3)") (class "Default")
      (node (ref "U$1") (pin "NC3") (pinfunction "NC3_NC3") (pintype "no_connect"))
    )
    (net (code "116") (name "unconnected-(U$1-PadNC4)") (class "Default")
      (node (ref "U$1") (pin "NC4") (pinfunction "NC4_NC4") (pintype "no_connect"))
    )
    (net (code "117") (name "unconnected-(U$1-PadNC5-PD8)") (class "Default")
      (node (ref "U$1") (pin "NC5-PD8") (pinfunction "NC5-PD8_NC5-PD8") (pintype "bidirectional"))
    )
    (net (code "118") (name "unconnected-(U$1-PadNC6-PB11)") (class "Default")
      (node (ref "U$1") (pin "NC6-PB11") (pinfunction "NC6-PB11_NC6-PB11") (pintype "no_connect"))
    )
    (net (code "119") (name "unconnected-(U$1-PadNC7-PF5)") (class "Default")
      (node (ref "U$1") (pin "NC7-PF5") (pinfunction "NC7-PF5_NC7-PF5") (pintype "bidirectional"))
    )
    (net (code "120") (name "unconnected-(U$1-PadNC8-PF4)") (class "Default")
      (node (ref "U$1") (pin "NC8-PF4") (pinfunction "NC8-PF4_NC8-PF4") (pintype "bidirectional"))
    )
    (net (code "121") (name "unconnected-(U$1-PadNRESET)") (class "Default")
      (node (ref "U$1") (pin "NRESET") (pinfunction "NRESET_NRESET") (pintype "input"))
    )
    (net (code "122") (name "unconnected-(U$1-PadPA0)") (class "Default")
      (node (ref "U$1") (pin "PA0") (pinfunction "PA0_PA0") (pintype "bidirectional"))
    )
    (net (code "123") (name "unconnected-(U$1-PadPA1)") (class "Default")
      (node (ref "U$1") (pin "PA1") (pinfunction "PA1_PA1") (pintype "bidirectional"))
    )
    (net (code "124") (name "unconnected-(U$1-PadPA2)") (class "Default")
      (node (ref "U$1") (pin "PA2") (pinfunction "PA2_PA2") (pintype "bidirectional"))
    )
    (net (code "125") (name "unconnected-(U$1-PadPA3)") (class "Default")
      (node (ref "U$1") (pin "PA3") (pinfunction "PA3_PA3") (pintype "bidirectional"))
    )
    (net (code "126") (name "unconnected-(U$1-PadPA4)") (class "Default")
      (node (ref "U$1") (pin "PA4") (pinfunction "PA4_PA4") (pintype "bidirectional"))
    )
    (net (code "127") (name "unconnected-(U$1-PadPA5)") (class "Default")
      (node (ref "U$1") (pin "PA5") (pinfunction "PA5_PA5") (pintype "bidirectional"))
    )
    (net (code "128") (name "unconnected-(U$1-PadPA6)") (class "Default")
      (node (ref "U$1") (pin "PA6") (pinfunction "PA6_PA6") (pintype "bidirectional"))
    )
    (net (code "129") (name "unconnected-(U$1-PadPA7)") (class "Default")
      (node (ref "U$1") (pin "PA7") (pinfunction "PA7_PA7") (pintype "bidirectional"))
    )
    (net (code "130") (name "unconnected-(U$1-PadPA8)") (class "Default")
      (node (ref "U$1") (pin "PA8") (pinfunction "PA8_PA8") (pintype "bidirectional"))
    )
    (net (code "131") (name "unconnected-(U$1-PadPA9)") (class "Default")
      (node (ref "U$1") (pin "PA9") (pinfunction "PA9_PA9") (pintype "bidirectional"))
    )
    (net (code "132") (name "unconnected-(U$1-PadPA10)") (class "Default")
      (node (ref "U$1") (pin "PA10") (pinfunction "PA10_PA10") (pintype "bidirectional"))
    )
    (net (code "133") (name "unconnected-(U$1-PadPA11)") (class "Default")
      (node (ref "U$1") (pin "PA11") (pinfunction "PA11_PA11") (pintype "bidirectional"))
    )
    (net (code "134") (name "unconnected-(U$1-PadPA12)") (class "Default")
      (node (ref "U$1") (pin "PA12") (pinfunction "PA12_PA12") (pintype "bidirectional"))
    )
    (net (code "135") (name "unconnected-(U$1-PadPA13)") (class "Default")
      (node (ref "U$1") (pin "PA13") (pinfunction "PA13_PA13") (pintype "bidirectional"))
    )
    (net (code "136") (name "unconnected-(U$1-PadPA14)") (class "Default")
      (node (ref "U$1") (pin "PA14") (pinfunction "PA14_PA14") (pintype "bidirectional"))
    )
    (net (code "137") (name "unconnected-(U$1-PadPA15)") (class "Default")
      (node (ref "U$1") (pin "PA15") (pinfunction "PA15_PA15") (pintype "bidirectional"))
    )
    (net (code "138") (name "unconnected-(U$1-PadPB0)") (class "Default")
      (node (ref "U$1") (pin "PB0") (pinfunction "PB0_PB0") (pintype "bidirectional"))
    )
    (net (code "139") (name "unconnected-(U$1-PadPB1)") (class "Default")
      (node (ref "U$1") (pin "PB1") (pinfunction "PB1_PB1") (pintype "bidirectional"))
    )
    (net (code "140") (name "unconnected-(U$1-PadPB2)") (class "Default")
      (node (ref "U$1") (pin "PB2") (pinfunction "PB2_PB2") (pintype "bidirectional"))
    )
    (net (code "141") (name "unconnected-(U$1-PadPB3)") (class "Default")
      (node (ref "U$1") (pin "PB3") (pinfunction "PB3_PB3") (pintype "bidirectional"))
    )
    (net (code "142") (name "unconnected-(U$1-PadPB4)") (class "Default")
      (node (ref "U$1") (pin "PB4") (pinfunction "PB4_PB4") (pintype "bidirectional"))
    )
    (net (code "143") (name "unconnected-(U$1-PadPB5)") (class "Default")
      (node (ref "U$1") (pin "PB5") (pinfunction "PB5_PB5") (pintype "bidirectional"))
    )
    (net (code "144") (name "unconnected-(U$1-PadPB6)") (class "Default")
      (node (ref "U$1") (pin "PB6") (pinfunction "PB6_PB6") (pintype "bidirectional"))
    )
    (net (code "145") (name "unconnected-(U$1-PadPB7)") (class "Default")
      (node (ref "U$1") (pin "PB7") (pinfunction "PB7_PB7") (pintype "bidirectional"))
    )
    (net (code "146") (name "unconnected-(U$1-PadPB10)") (class "Default")
      (node (ref "U$1") (pin "PB10") (pinfunction "PB10_PB10") (pintype "bidirectional"))
    )
    (net (code "147") (name "unconnected-(U$1-PadPB12)") (class "Default")
      (node (ref "U$1") (pin "PB12") (pinfunction "PB12_PB12") (pintype "bidirectional"))
    )
    (net (code "148") (name "unconnected-(U$1-PadPB13)") (class "Default")
      (node (ref "U$1") (pin "PB13") (pinfunction "PB13_PB13") (pintype "bidirectional"))
    )
    (net (code "149") (name "unconnected-(U$1-PadPB14)") (class "Default")
      (node (ref "U$1") (pin "PB14") (pinfunction "PB14_PB14") (pintype "bidirectional"))
    )
    (net (code "150") (name "unconnected-(U$1-PadPB15)") (class "Default")
      (node (ref "U$1") (pin "PB15") (pinfunction "PB15_PB15") (pintype "bidirectional"))
    )
    (net (code "151") (name "unconnected-(U$1-PadPC0)") (class "Default")
      (node (ref "U$1") (pin "PC0") (pinfunction "PC0_PC0") (pintype "bidirectional"))
    )
    (net (code "152") (name "unconnected-(U$1-PadPC1)") (class "Default")
      (node (ref "U$1") (pin "PC1") (pinfunction "PC1_PC1") (pintype "bidirectional"))
    )
    (net (code "153") (name "unconnected-(U$1-PadPC2)") (class "Default")
      (node (ref "U$1") (pin "PC2") (pinfunction "PC2_PC2") (pintype "bidirectional"))
    )
    (net (code "154") (name "unconnected-(U$1-PadPC3)") (class "Default")
      (node (ref "U$1") (pin "PC3") (pinfunction "PC3_PC3") (pintype "bidirectional"))
    )
    (net (code "155") (name "unconnected-(U$1-PadPC4)") (class "Default")
      (node (ref "U$1") (pin "PC4") (pinfunction "PC4_PC4") (pintype "bidirectional"))
    )
    (net (code "156") (name "unconnected-(U$1-PadPC5)") (class "Default")
      (node (ref "U$1") (pin "PC5") (pinfunction "PC5_PC5") (pintype "bidirectional"))
    )
    (net (code "157") (name "unconnected-(U$1-PadPC6)") (class "Default")
      (node (ref "U$1") (pin "PC6") (pinfunction "PC6_PC6") (pintype "bidirectional"))
    )
    (net (code "158") (name "unconnected-(U$1-PadPC7)") (class "Default")
      (node (ref "U$1") (pin "PC7") (pinfunction "PC7_PC7") (pintype "bidirectional"))
    )
    (net (code "159") (name "unconnected-(U$1-PadPC8)") (class "Default")
      (node (ref "U$1") (pin "PC8") (pinfunction "PC8_PC8") (pintype "bidirectional"))
    )
    (net (code "160") (name "unconnected-(U$1-PadPC9)") (class "Default")
      (node (ref "U$1") (pin "PC9") (pinfunction "PC9_PC9") (pintype "bidirectional"))
    )
    (net (code "161") (name "unconnected-(U$1-PadPC10)") (class "Default")
      (node (ref "U$1") (pin "PC10") (pinfunction "PC10_PC10") (pintype "bidirectional"))
    )
    (net (code "162") (name "unconnected-(U$1-PadPC11)") (class "Default")
      (node (ref "U$1") (pin "PC11") (pinfunction "PC11_PC11") (pintype "bidirectional"))
    )
    (net (code "163") (name "unconnected-(U$1-PadPC12)") (class "Default")
      (node (ref "U$1") (pin "PC12") (pinfunction "PC12_PC12") (pintype "bidirectional"))
    )
    (net (code "164") (name "unconnected-(U$1-PadPC13)") (class "Default")
      (node (ref "U$1") (pin "PC13") (pinfunction "PC13_PC13") (pintype "bidirectional"))
    )
    (net (code "165") (name "unconnected-(U$1-PadPC14)") (class "Default")
      (node (ref "U$1") (pin "PC14") (pinfunction "PC14_PC14") (pintype "bidirectional"))
    )
    (net (code "166") (name "unconnected-(U$1-PadPC15)") (class "Default")
      (node (ref "U$1") (pin "PC15") (pinfunction "PC15_PC15") (pintype "bidirectional"))
    )
    (net (code "167") (name "unconnected-(U$1-PadPD2)") (class "Default")
      (node (ref "U$1") (pin "PD2") (pinfunction "PD2_PD2") (pintype "bidirectional"))
    )
    (net (code "168") (name "unconnected-(U$1-PadPF0-PH0)") (class "Default")
      (node (ref "U$1") (pin "PF0-PH0") (pinfunction "PF0-PH0_PF0-PH0") (pintype "bidirectional"))
    )
    (net (code "169") (name "unconnected-(U$1-PadPF1-PH1)") (class "Default")
      (node (ref "U$1") (pin "PF1-PH1") (pinfunction "PF1-PH1_PF1-PH1") (pintype "bidirectional"))
    )
  )
)
